# COMS0005_Comms_Test_Board.net
KiCad netlist of a schematic drawn in Altium Designer
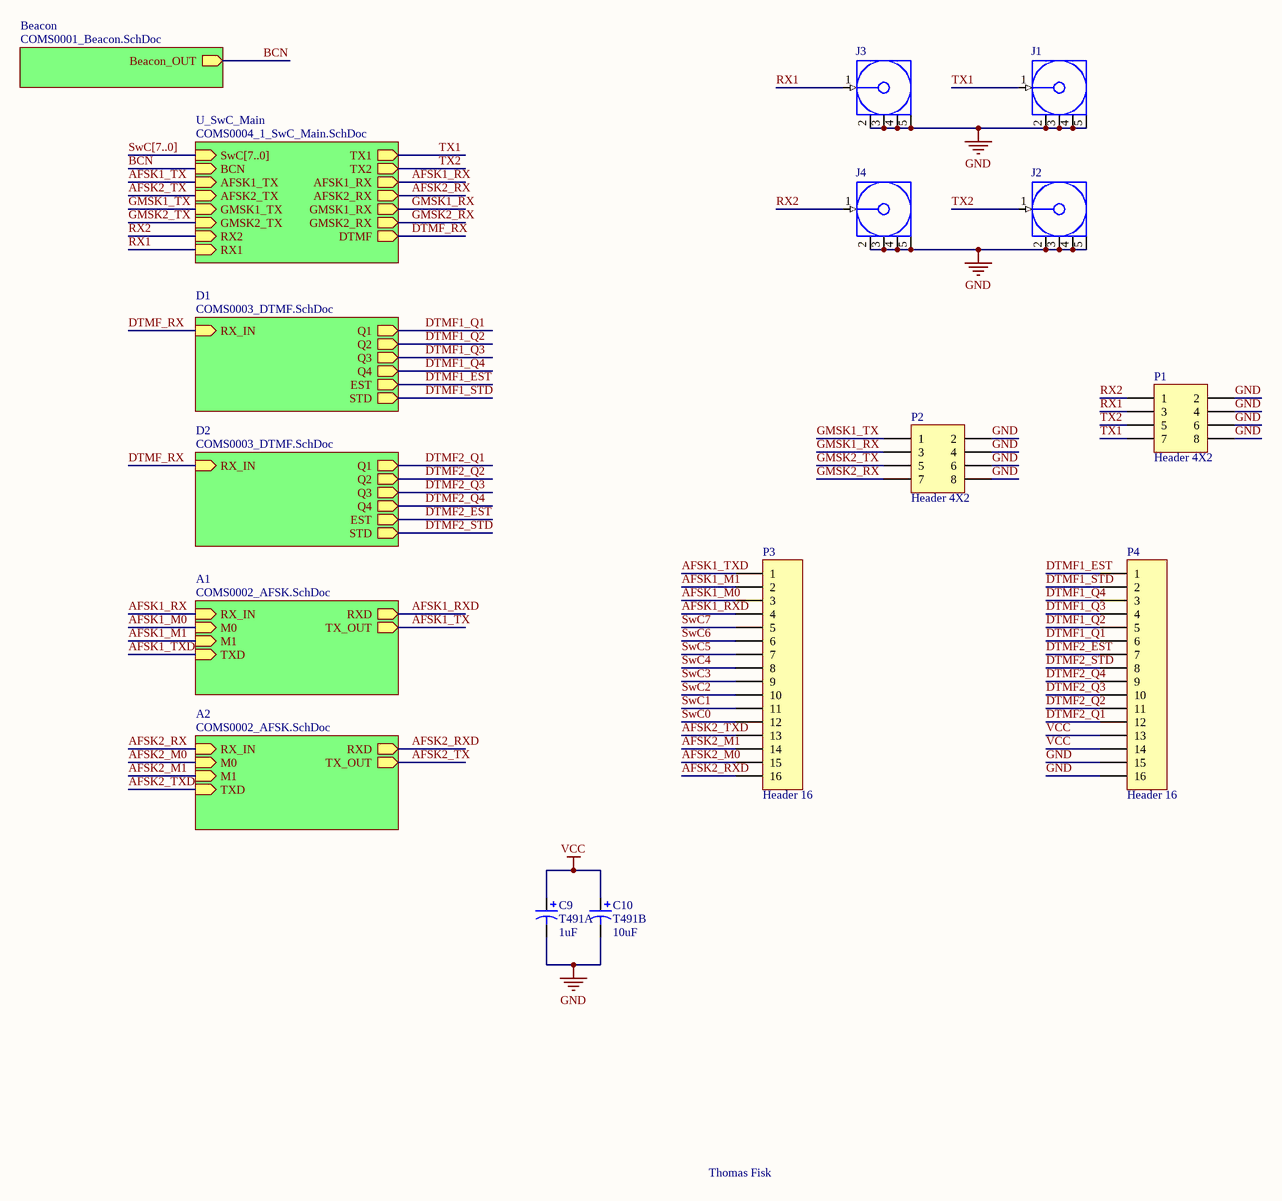
[diagram p0: COMS0005_Comms_Test_Board.SchDoc]

(export (version "E")
  (design (tool "Eeschema 10.0.6"))
  (components
    (comp (ref "C9")
      (value "T491A")
      (footprint "A")
      (description "Solid Tantalum Chip Capacitor, Standard T491 Series - Industrial Grade")
      (fields (field (name "ALTIUM_VALUE") "1uF") (field (name "PUBLISHER") "Altium Limited"))
      (libsource (lib "KEMET Chip Capacitor") (part "T491A"))
    )
    (comp (ref "C10")
      (value "T491B")
      (footprint "B")
      (description "Solid Tantalum Chip Capacitor, Standard T491 Series - Industrial Grade")
      (fields (field (name "ALTIUM_VALUE") "10uF") (field (name "PUBLISHER") "Altium Limited"))
      (libsource (lib "KEMET Chip Capacitor") (part "T491B"))
    )
    (comp (ref "J1")
      (value "TX1")
      (footprint "SMB_V-RJ45")
      (fields (field (name "PUBLISHER") "Altium Limited"))
      (libsource (lib "Miscellaneous Connectors") (part "COAX-F"))
    )
    (comp (ref "J2")
      (value "TX2")
      (footprint "SMB_V-RJ45")
      (fields (field (name "PUBLISHER") "Altium Limited"))
      (libsource (lib "Miscellaneous Connectors") (part "COAX-F"))
    )
    (comp (ref "J3")
      (value "RX2")
      (footprint "SMB_V-RJ45")
      (fields (field (name "PUBLISHER") "Altium Limited"))
      (libsource (lib "Miscellaneous Connectors") (part "COAX-F"))
    )
    (comp (ref "J4")
      (value "RX1")
      (footprint "SMB_V-RJ45")
      (fields (field (name "PUBLISHER") "Altium Limited"))
      (libsource (lib "Miscellaneous Connectors") (part "COAX-F"))
    )
    (comp (ref "P1")
      (value "Header 4X2")
      (footprint "HDR2X4")
      (description "Header, 4-Pin, Dual row")
      (fields (field (name "PUBLISHER") "Altium Limited"))
      (libsource (lib "Miscellaneous Connectors") (part "Header 4X2"))
    )
    (comp (ref "P2")
      (value "Header 4X2")
      (footprint "HDR2X4")
      (description "Header, 4-Pin, Dual row")
      (fields (field (name "PUBLISHER") "Altium Limited"))
      (libsource (lib "Miscellaneous Connectors") (part "Header 4X2"))
    )
    (comp (ref "P3")
      (value "Header 16")
      (footprint "HDR1X16")
      (description "Header, 16-Pin")
      (fields (field (name "PUBLISHER") "Altium Limited"))
      (libsource (lib "Miscellaneous Connectors") (part "Header 16"))
    )
    (comp (ref "P4")
      (value "Header 16")
      (footprint "HDR1X16")
      (description "Header, 16-Pin")
      (fields (field (name "PUBLISHER") "Altium Limited"))
      (libsource (lib "Miscellaneous Connectors") (part "Header 16"))
    )
  )
  (nets
    (net (code "1") (name "/AFSK1_M0") (class "Default")
      (node (ref "P3") (pin "3") (pinfunction "3_3") (pintype "passive"))
    )
    (net (code "2") (name "/AFSK1_M1") (class "Default")
      (node (ref "P3") (pin "2") (pinfunction "2_2") (pintype "passive"))
    )
    (net (code "4") (name "/AFSK1_RXD") (class "Default")
      (node (ref "P3") (pin "4") (pinfunction "4_4") (pintype "passive"))
    )
    (net (code "6") (name "/AFSK1_TXD") (class "Default")
      (node (ref "P3") (pin "1") (pinfunction "1_1") (pintype "passive"))
    )
    (net (code "7") (name "/AFSK2_M0") (class "Default")
      (node (ref "P3") (pin "15") (pinfunction "15_15") (pintype "passive"))
    )
    (net (code "8") (name "/AFSK2_M1") (class "Default")
      (node (ref "P3") (pin "14") (pinfunction "14_14") (pintype "passive"))
    )
    (net (code "10") (name "/AFSK2_RXD") (class "Default")
      (node (ref "P3") (pin "16") (pinfunction "16_16") (pintype "passive"))
    )
    (net (code "12") (name "/AFSK2_TXD") (class "Default")
      (node (ref "P3") (pin "13") (pinfunction "13_13") (pintype "passive"))
    )
    (net (code "14") (name "/DTMF1_EST") (class "Default")
      (node (ref "P4") (pin "1") (pinfunction "1_1") (pintype "passive"))
    )
    (net (code "15") (name "/DTMF1_Q1") (class "Default")
      (node (ref "P4") (pin "6") (pinfunction "6_6") (pintype "passive"))
    )
    (net (code "16") (name "/DTMF1_Q2") (class "Default")
      (node (ref "P4") (pin "5") (pinfunction "5_5") (pintype "passive"))
    )
    (net (code "17") (name "/DTMF1_Q3") (class "Default")
      (node (ref "P4") (pin "4") (pinfunction "4_4") (pintype "passive"))
    )
    (net (code "18") (name "/DTMF1_Q4") (class "Default")
      (node (ref "P4") (pin "3") (pinfunction "3_3") (pintype "passive"))
    )
    (net (code "19") (name "/DTMF1_STD") (class "Default")
      (node (ref "P4") (pin "2") (pinfunction "2_2") (pintype "passive"))
    )
    (net (code "20") (name "/DTMF2_EST") (class "Default")
      (node (ref "P4") (pin "7") (pinfunction "7_7") (pintype "passive"))
    )
    (net (code "21") (name "/DTMF2_Q1") (class "Default")
      (node (ref "P4") (pin "12") (pinfunction "12_12") (pintype "passive"))
    )
    (net (code "22") (name "/DTMF2_Q2") (class "Default")
      (node (ref "P4") (pin "11") (pinfunction "11_11") (pintype "passive"))
    )
    (net (code "23") (name "/DTMF2_Q3") (class "Default")
      (node (ref "P4") (pin "10") (pinfunction "10_10") (pintype "passive"))
    )
    (net (code "24") (name "/DTMF2_Q4") (class "Default")
      (node (ref "P4") (pin "9") (pinfunction "9_9") (pintype "passive"))
    )
    (net (code "25") (name "/DTMF2_STD") (class "Default")
      (node (ref "P4") (pin "8") (pinfunction "8_8") (pintype "passive"))
    )
    (net (code "27") (name "/GMSK1_RX") (class "Default")
      (node (ref "P2") (pin "3") (pinfunction "3_3") (pintype "passive"))
    )
    (net (code "28") (name "/GMSK1_TX") (class "Default")
      (node (ref "P2") (pin "1") (pinfunction "1_1") (pintype "passive"))
    )
    (net (code "29") (name "/GMSK2_RX") (class "Default")
      (node (ref "P2") (pin "7") (pinfunction "7_7") (pintype "passive"))
    )
    (net (code "30") (name "/GMSK2_TX") (class "Default")
      (node (ref "P2") (pin "5") (pinfunction "5_5") (pintype "passive"))
    )
    (net (code "31") (name "/RX1") (class "Default")
      (node (ref "J3") (pin "1") (pinfunction "Signal_1") (pintype "input"))
      (node (ref "P1") (pin "3") (pinfunction "3_3") (pintype "passive"))
    )
    (net (code "32") (name "/RX2") (class "Default")
      (node (ref "J4") (pin "1") (pinfunction "Signal_1") (pintype "input"))
      (node (ref "P1") (pin "1") (pinfunction "1_1") (pintype "passive"))
    )
    (net (code "33") (name "/SwC0") (class "Default")
      (node (ref "P3") (pin "12") (pinfunction "12_12") (pintype "passive"))
    )
    (net (code "34") (name "/SwC1") (class "Default")
      (node (ref "P3") (pin "11") (pinfunction "11_11") (pintype "passive"))
    )
    (net (code "35") (name "/SwC2") (class "Default")
      (node (ref "P3") (pin "10") (pinfunction "10_10") (pintype "passive"))
    )
    (net (code "36") (name "/SwC3") (class "Default")
      (node (ref "P3") (pin "9") (pinfunction "9_9") (pintype "passive"))
    )
    (net (code "37") (name "/SwC4") (class "Default")
      (node (ref "P3") (pin "8") (pinfunction "8_8") (pintype "passive"))
    )
    (net (code "38") (name "/SwC5") (class "Default")
      (node (ref "P3") (pin "7") (pinfunction "7_7") (pintype "passive"))
    )
    (net (code "39") (name "/SwC6") (class "Default")
      (node (ref "P3") (pin "6") (pinfunction "6_6") (pintype "passive"))
    )
    (net (code "40") (name "/SwC7") (class "Default")
      (node (ref "P3") (pin "5") (pinfunction "5_5") (pintype "passive"))
    )
    (net (code "42") (name "/TX1") (class "Default")
      (node (ref "J1") (pin "1") (pinfunction "Signal_1") (pintype "input"))
      (node (ref "P1") (pin "7") (pinfunction "7_7") (pintype "passive"))
    )
    (net (code "43") (name "/TX2") (class "Default")
      (node (ref "J2") (pin "1") (pinfunction "Signal_1") (pintype "input"))
      (node (ref "P1") (pin "5") (pinfunction "5_5") (pintype "passive"))
    )
    (net (code "44") (name "GND") (class "Default")
      (node (ref "C10") (pin "2") (pinfunction "2_2") (pintype "passive"))
      (node (ref "C9") (pin "2") (pinfunction "2_2") (pintype "passive"))
      (node (ref "J1") (pin "2") (pinfunction "GND_2") (pintype "power_in"))
      (node (ref "J1") (pin "3") (pinfunction "GND_3") (pintype "power_in"))
      (node (ref "J1") (pin "4") (pinfunction "GND_4") (pintype "power_in"))
      (node (ref "J1") (pin "5") (pinfunction "GND_5") (pintype "power_in"))
      (node (ref "J2") (pin "2") (pinfunction "GND_2") (pintype "power_in"))
      (node (ref "J2") (pin "3") (pinfunction "GND_3") (pintype "power_in"))
      (node (ref "J2") (pin "4") (pinfunction "GND_4") (pintype "power_in"))
      (node (ref "J2") (pin "5") (pinfunction "GND_5") (pintype "power_in"))
      (node (ref "J3") (pin "2") (pinfunction "GND_2") (pintype "power_in"))
      (node (ref "J3") (pin "3") (pinfunction "GND_3") (pintype "power_in"))
      (node (ref "J3") (pin "4") (pinfunction "GND_4") (pintype "power_in"))
      (node (ref "J3") (pin "5") (pinfunction "GND_5") (pintype "power_in"))
      (node (ref "J4") (pin "2") (pinfunction "GND_2") (pintype "power_in"))
      (node (ref "J4") (pin "3") (pinfunction "GND_3") (pintype "power_in"))
      (node (ref "J4") (pin "4") (pinfunction "GND_4") (pintype "power_in"))
      (node (ref "J4") (pin "5") (pinfunction "GND_5") (pintype "power_in"))
      (node (ref "P1") (pin "2") (pinfunction "2_2") (pintype "passive"))
      (node (ref "P1") (pin "4") (pinfunction "4_4") (pintype "passive"))
      (node (ref "P1") (pin "6") (pinfunction "6_6") (pintype "passive"))
      (node (ref "P1") (pin "8") (pinfunction "8_8") (pintype "passive"))
      (node (ref "P2") (pin "2") (pinfunction "2_2") (pintype "passive"))
      (node (ref "P2") (pin "4") (pinfunction "4_4") (pintype "passive"))
      (node (ref "P2") (pin "6") (pinfunction "6_6") (pintype "passive"))
      (node (ref "P2") (pin "8") (pinfunction "8_8") (pintype "passive"))
      (node (ref "P4") (pin "15") (pinfunction "15_15") (pintype "passive"))
      (node (ref "P4") (pin "16") (pinfunction "16_16") (pintype "passive"))
    )
    (net (code "45") (name "VCC") (class "Default")
      (node (ref "C10") (pin "1") (pinfunction "1_1") (pintype "passive"))
      (node (ref "C9") (pin "1") (pinfunction "1_1") (pintype "passive"))
      (node (ref "P4") (pin "13") (pinfunction "13_13") (pintype "passive"))
      (node (ref "P4") (pin "14") (pinfunction "14_14") (pintype "passive"))
    )
  )
)
